# Temperature_Sensor.net
KiCad netlist of a schematic drawn in EAGLE
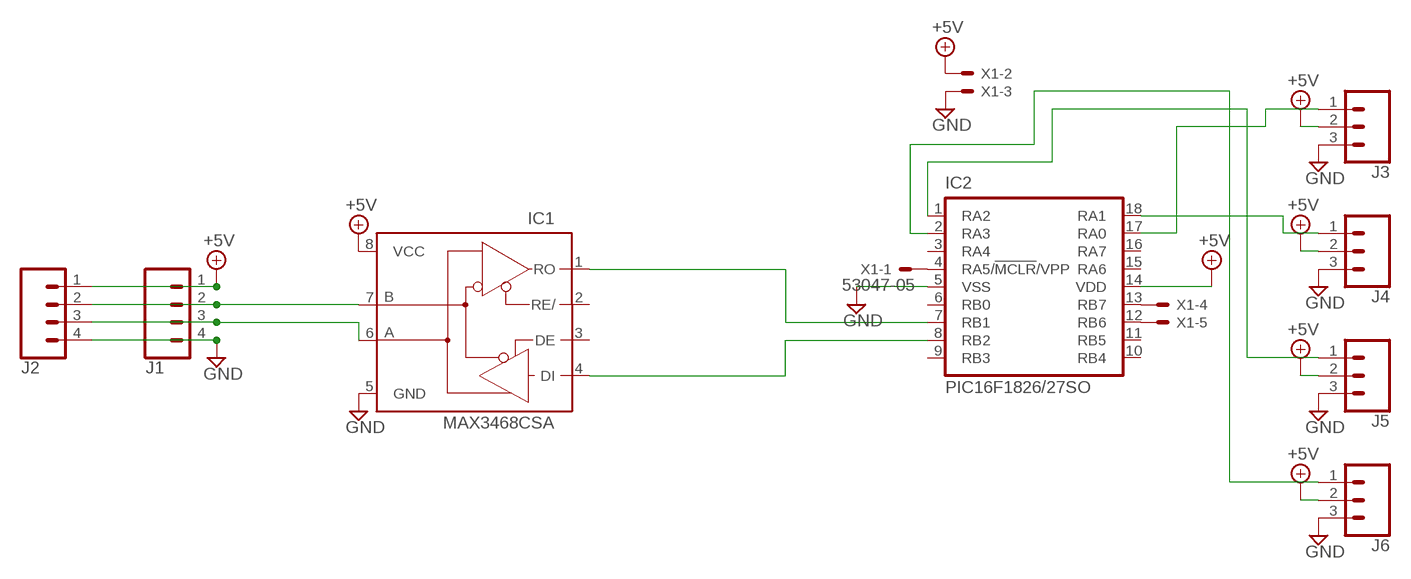
[diagram p0: schematic, sheet 1]

(export (version "E")
  (design (tool "Eeschema 10.0.6"))
  (components
    (comp (ref "IC1")
      (value "MAX3468CSA")
      (footprint "eagle-import:SO08")
      (fields (field (name "MPN") "MAX3468CSA+"))
      (libsource (lib "eagle-import") (part "MAX34SA68C"))
    )
    (comp (ref "IC2")
      (value "PIC16F1826/27SO")
      (footprint "eagle-import:SO-18W")
      (libsource (lib "eagle-import") (part "PIC16F1826/27SO"))
    )
    (comp (ref "J1")
      (value "CONN_04SCREW")
      (footprint "eagle-import:SCREWTERMINAL-3.5MM-4")
      (libsource (lib "eagle-import") (part "CONN_04SCREW"))
    )
    (comp (ref "J2")
      (value "CONN_04SCREW")
      (footprint "eagle-import:SCREWTERMINAL-3.5MM-4")
      (libsource (lib "eagle-import") (part "CONN_04SCREW"))
    )
    (comp (ref "J3")
      (value "CONN_03")
      (footprint "eagle-import:1X03")
      (libsource (lib "eagle-import") (part "CONN_03"))
    )
    (comp (ref "J4")
      (value "CONN_03")
      (footprint "eagle-import:1X03")
      (libsource (lib "eagle-import") (part "CONN_03"))
    )
    (comp (ref "J5")
      (value "CONN_03")
      (footprint "eagle-import:1X03")
      (libsource (lib "eagle-import") (part "CONN_03"))
    )
    (comp (ref "J6")
      (value "CONN_03")
      (footprint "eagle-import:1X03")
      (libsource (lib "eagle-import") (part "CONN_03"))
    )
    (comp (ref "X1")
      (value "53047-05")
      (footprint "eagle-import:53047-05")
      (fields (field (name "MF") "MOLEX") (field (name "MPN") "53047-0510"))
      (libsource (lib "eagle-import") (part "53?-05047"))
    )
  )
  (nets
    (net (code "1") (name "+5V") (class "Default")
      (node (ref "IC1") (pin "8") (pinfunction "VCC_8") (pintype "power_in"))
      (node (ref "IC2") (pin "14") (pinfunction "VDD_14") (pintype "power_in"))
      (node (ref "J1") (pin "1") (pinfunction "1_1") (pintype "passive"))
      (node (ref "J2") (pin "1") (pinfunction "1_1") (pintype "passive"))
      (node (ref "J3") (pin "2") (pinfunction "2_2") (pintype "passive"))
      (node (ref "J4") (pin "2") (pinfunction "2_2") (pintype "passive"))
      (node (ref "J5") (pin "2") (pinfunction "2_2") (pintype "passive"))
      (node (ref "J6") (pin "2") (pinfunction "2_2") (pintype "passive"))
      (node (ref "X1") (pin "2") (pinfunction "S_2") (pintype "passive"))
    )
    (net (code "2") (name "GND") (class "Default")
      (node (ref "IC1") (pin "5") (pinfunction "GND_5") (pintype "power_in"))
      (node (ref "IC2") (pin "5") (pinfunction "VSS_5") (pintype "power_in"))
      (node (ref "J1") (pin "4") (pinfunction "4_4") (pintype "passive"))
      (node (ref "J2") (pin "4") (pinfunction "4_4") (pintype "passive"))
      (node (ref "J3") (pin "3") (pinfunction "3_3") (pintype "passive"))
      (node (ref "J4") (pin "3") (pinfunction "3_3") (pintype "passive"))
      (node (ref "J5") (pin "3") (pinfunction "3_3") (pintype "passive"))
      (node (ref "J6") (pin "3") (pinfunction "3_3") (pintype "passive"))
      (node (ref "X1") (pin "3") (pinfunction "S_3") (pintype "passive"))
    )
    (net (code "3") (name "Net-(IC1-A)") (class "Default")
      (node (ref "IC1") (pin "6") (pinfunction "A_6") (pintype "passive"))
      (node (ref "J1") (pin "3") (pinfunction "3_3") (pintype "passive"))
      (node (ref "J2") (pin "3") (pinfunction "3_3") (pintype "passive"))
    )
    (net (code "4") (name "Net-(IC1-B)") (class "Default")
      (node (ref "IC1") (pin "7") (pinfunction "B_7") (pintype "passive"))
      (node (ref "J1") (pin "2") (pinfunction "2_2") (pintype "passive"))
      (node (ref "J2") (pin "2") (pinfunction "2_2") (pintype "passive"))
    )
    (net (code "5") (name "Net-(IC1-DI)") (class "Default")
      (node (ref "IC1") (pin "4") (pinfunction "DI_4") (pintype "input"))
      (node (ref "IC2") (pin "8") (pinfunction "RB2_8") (pintype "bidirectional"))
    )
    (net (code "6") (name "Net-(IC1-RO)") (class "Default")
      (node (ref "IC1") (pin "1") (pinfunction "RO_1") (pintype "output"))
      (node (ref "IC2") (pin "7") (pinfunction "RB1_7") (pintype "bidirectional"))
    )
    (net (code "7") (name "Net-(IC2-RA0)") (class "Default")
      (node (ref "IC2") (pin "17") (pinfunction "RA0_17") (pintype "bidirectional"))
      (node (ref "J3") (pin "1") (pinfunction "1_1") (pintype "passive"))
    )
    (net (code "8") (name "Net-(IC2-RA1)") (class "Default")
      (node (ref "IC2") (pin "18") (pinfunction "RA1_18") (pintype "bidirectional"))
      (node (ref "J4") (pin "1") (pinfunction "1_1") (pintype "passive"))
    )
    (net (code "9") (name "Net-(IC2-RA2)") (class "Default")
      (node (ref "IC2") (pin "1") (pinfunction "RA2_1") (pintype "bidirectional"))
      (node (ref "J5") (pin "1") (pinfunction "1_1") (pintype "passive"))
    )
    (net (code "10") (name "Net-(IC2-RA3)") (class "Default")
      (node (ref "IC2") (pin "2") (pinfunction "RA3_2") (pintype "bidirectional"))
      (node (ref "J6") (pin "1") (pinfunction "1_1") (pintype "passive"))
    )
    (net (code "11") (name "Net-(IC2-RA5{slash}~{MCLR}{slash}VPP)") (class "Default")
      (node (ref "IC2") (pin "4") (pinfunction "RA5/~{MCLR}/VPP_4") (pintype "bidirectional"))
      (node (ref "X1") (pin "1") (pinfunction "S_1") (pintype "passive"))
    )
    (net (code "12") (name "Net-(IC2-RB6)") (class "Default")
      (node (ref "IC2") (pin "12") (pinfunction "RB6_12") (pintype "bidirectional"))
      (node (ref "X1") (pin "5") (pinfunction "S_5") (pintype "passive"))
    )
    (net (code "13") (name "Net-(IC2-RB7)") (class "Default")
      (node (ref "IC2") (pin "13") (pinfunction "RB7_13") (pintype "bidirectional"))
      (node (ref "X1") (pin "4") (pinfunction "S_4") (pintype "passive"))
    )
    (net (code "14") (name "unconnected-(IC1-DE-Pad3)") (class "Default")
      (node (ref "IC1") (pin "3") (pinfunction "DE_3") (pintype "input"))
    )
    (net (code "15") (name "unconnected-(IC1-RE{slash}-Pad2)") (class "Default")
      (node (ref "IC1") (pin "2") (pinfunction "RE/_2") (pintype "input"))
    )
    (net (code "16") (name "unconnected-(IC2-RA4-Pad3)") (class "Default")
      (node (ref "IC2") (pin "3") (pinfunction "RA4_3") (pintype "bidirectional"))
    )
    (net (code "17") (name "unconnected-(IC2-RA6-Pad15)") (class "Default")
      (node (ref "IC2") (pin "15") (pinfunction "RA6_15") (pintype "bidirectional"))
    )
    (net (code "18") (name "unconnected-(IC2-RA7-Pad16)") (class "Default")
      (node (ref "IC2") (pin "16") (pinfunction "RA7_16") (pintype "bidirectional"))
    )
    (net (code "19") (name "unconnected-(IC2-RB0-Pad6)") (class "Default")
      (node (ref "IC2") (pin "6") (pinfunction "RB0_6") (pintype "bidirectional"))
    )
    (net (code "20") (name "unconnected-(IC2-RB3-Pad9)") (class "Default")
      (node (ref "IC2") (pin "9") (pinfunction "RB3_9") (pintype "bidirectional"))
    )
    (net (code "21") (name "unconnected-(IC2-RB4-Pad10)") (class "Default")
      (node (ref "IC2") (pin "10") (pinfunction "RB4_10") (pintype "bidirectional"))
    )
    (net (code "22") (name "unconnected-(IC2-RB5-Pad11)") (class "Default")
      (node (ref "IC2") (pin "11") (pinfunction "RB5_11") (pintype "bidirectional"))
    )
  )
)
